# v0_3_1.net
KiCad netlist of a schematic drawn in EAGLE
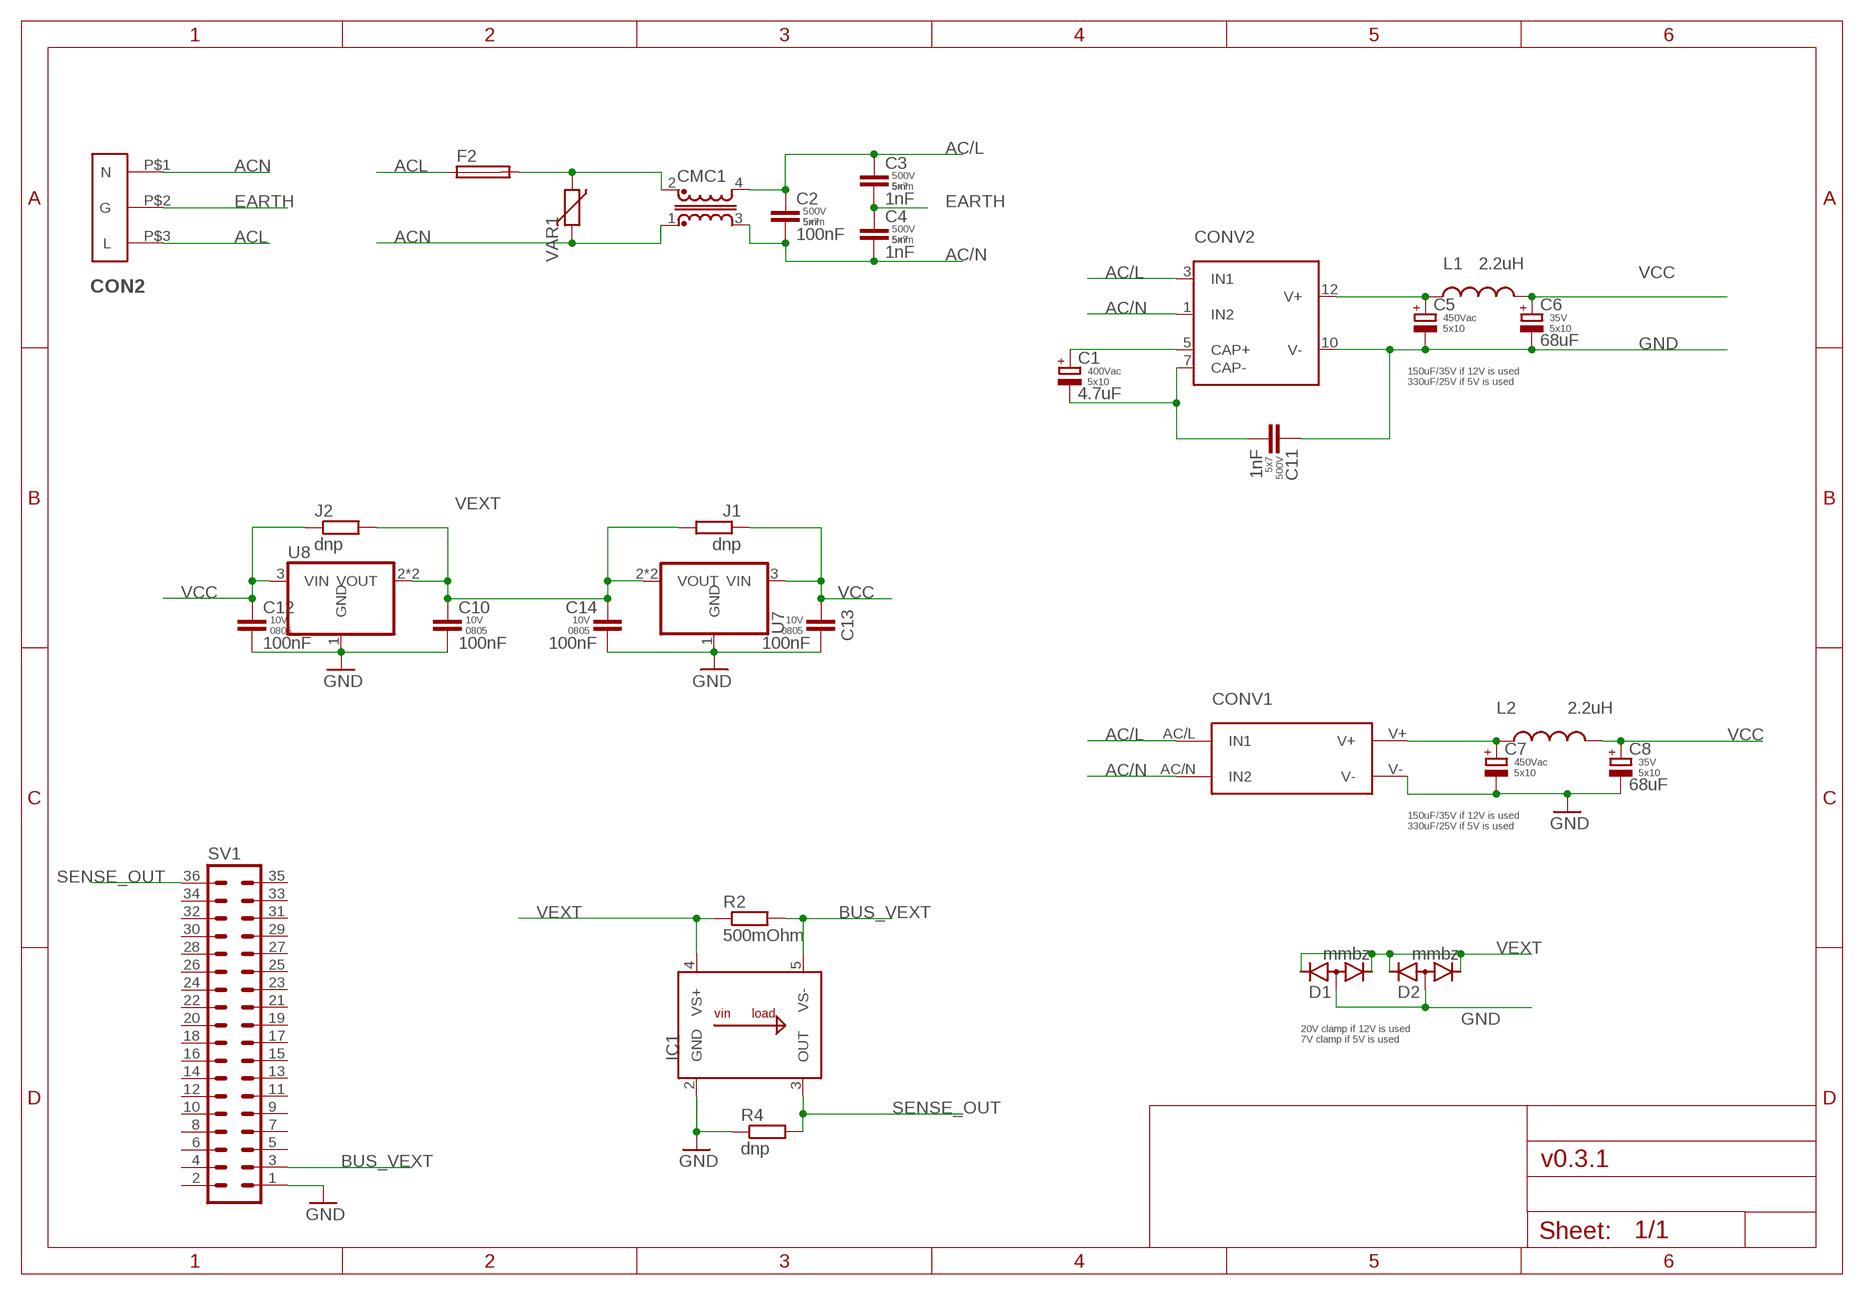
[diagram p0: schematic, sheet 1]

(export (version "E")
  (design (tool "Eeschema 10.0.6"))
  (components
    (comp (ref "C1")
      (value "4.7uF")
      (footprint "eagle-import:CAPPRD508W65D1000H1600B")
      (fields
        (field (name "PACKAGE") "5x10")
        (field (name "RATING") "450Vac")
        (field (name "RATING_1") "400Vac")
      )
      (libsource (lib "eagle-import") (part "CAP-POL-5PX10WX16H"))
    )
    (comp (ref "C2")
      (value "100nF")
      (footprint "eagle-import:C050-025X075")
      (fields
        (field (name "RATING") "500V")
        (field (name "DIMENSIONS") "5mm")
        (field (name "RATING_1") "500V")
      )
      (libsource (lib "eagle-import") (part "CAP-P5W6H8T2.5"))
    )
    (comp (ref "C3")
      (value "1nF")
      (footprint "eagle-import:C050-025X075")
      (fields
        (field (name "RATING") "500V")
        (field (name "DIMENSIONS") "5mm")
        (field (name "RATING_1") "500V")
      )
      (libsource (lib "eagle-import") (part "CAP-P5W6H8T2.5"))
    )
    (comp (ref "C4")
      (value "1nF")
      (footprint "eagle-import:C050-025X075")
      (fields
        (field (name "RATING") "500V")
        (field (name "DIMENSIONS") "5mm")
        (field (name "RATING_1") "500V")
      )
      (libsource (lib "eagle-import") (part "CAP-P5W6H8T2.5"))
    )
    (comp (ref "C5")
      (value "CAP-POL-5PX10WX16H")
      (footprint "eagle-import:CAPPRD508W65D1000H1600B")
      (libsource (lib "eagle-import") (part "CAP-POL-5PX10WX16H"))
    )
    (comp (ref "C6")
      (value "68uF")
      (footprint "eagle-import:CAPPRD508W65D1000H1600B")
      (fields
        (field (name "PACKAGE") "5x10")
        (field (name "RATING") "450Vac")
        (field (name "RATING_1") "35V")
      )
      (libsource (lib "eagle-import") (part "CAP-POL-5PX10WX16H"))
    )
    (comp (ref "C7")
      (value "CAP-POL-5PX10WX16H")
      (footprint "eagle-import:CAPPRD508W65D1000H1600B")
      (libsource (lib "eagle-import") (part "CAP-POL-5PX10WX16H"))
    )
    (comp (ref "C8")
      (value "68uF")
      (footprint "eagle-import:CAPPRD508W65D1000H1600B")
      (fields
        (field (name "PACKAGE") "5x10")
        (field (name "RATING") "450Vac")
        (field (name "RATING_1") "35V")
      )
      (libsource (lib "eagle-import") (part "CAP-POL-5PX10WX16H"))
    )
    (comp (ref "C10")
      (value "100nF")
      (footprint "eagle-import:C0805")
      (fields (field (name "RATING") "10V") (field (name "PACKAGE") "0805"))
      (libsource (lib "eagle-import") (part "CAP-0805"))
    )
    (comp (ref "C11")
      (value "1nF")
      (footprint "eagle-import:C050-025X075")
      (fields (field (name "RATING") "500V") (field (name "PACKAGE") "5x7"))
      (libsource (lib "eagle-import") (part "CAP-P5W6H8T2.5"))
    )
    (comp (ref "C12")
      (value "100nF")
      (footprint "eagle-import:C0805")
      (libsource (lib "eagle-import") (part "CAP-0805"))
    )
    (comp (ref "C13")
      (value "100nF")
      (footprint "eagle-import:C0805")
      (libsource (lib "eagle-import") (part "CAP-0805"))
    )
    (comp (ref "C14")
      (value "100nF")
      (footprint "eagle-import:C0805")
      (fields (field (name "RATING") "10V") (field (name "PACKAGE") "0805"))
      (libsource (lib "eagle-import") (part "CAP-0805"))
    )
    (comp (ref "CMC1")
      (value "DLD-302U-1A")
      (footprint "eagle-import:DLD")
      (libsource (lib "eagle-import") (part "DLD-302U-1A"))
    )
    (comp (ref "CON2")
      (value "4300.0101")
      (footprint "eagle-import:IEC-C6")
      (libsource (lib "eagle-import") (part "4300.0101"))
    )
    (comp (ref "CONV1")
      (value "IRM-03-12V")
      (footprint "eagle-import:IRM-03")
      (libsource (lib "eagle-import") (part "IRM-03-12V"))
    )
    (comp (ref "CONV2")
      (value "AMEOF312SJZ")
      (footprint "eagle-import:AMEOF3-JZ")
      (libsource (lib "eagle-import") (part "AMEOF312SJZ"))
    )
    (comp (ref "D1")
      (value "mmbz")
      (footprint "eagle-import:SOT23")
      (libsource (lib "eagle-import") (part "DIODE-2CA|ACSOT23"))
    )
    (comp (ref "D2")
      (value "mmbz")
      (footprint "eagle-import:SOT23")
      (libsource (lib "eagle-import") (part "DIODE-2CA|ACSOT23"))
    )
    (comp (ref "F2")
      (value "ZH8")
      (footprint "eagle-import:ZH8X2")
      (libsource (lib "eagle-import") (part "ZH8"))
    )
    (comp (ref "IC1")
      (value "ZXCT1021")
      (footprint "eagle-import:SOT95P240X110-5")
      (libsource (lib "eagle-import") (part "ZXCT1021"))
    )
    (comp (ref "J1")
      (value "dnp")
      (footprint "eagle-import:R0805")
      (libsource (lib "eagle-import") (part "R-EU_R0805"))
    )
    (comp (ref "J2")
      (value "dnp")
      (footprint "eagle-import:R0805")
      (libsource (lib "eagle-import") (part "R-EU_R0805"))
    )
    (comp (ref "L1")
      (value "2.2uH")
      (footprint "eagle-import:COIL0608")
      (libsource (lib "eagle-import") (part "COIL0608-0.022"))
    )
    (comp (ref "L2")
      (value "2.2uH")
      (footprint "eagle-import:COIL0608")
      (libsource (lib "eagle-import") (part "COIL0608-0.022"))
    )
    (comp (ref "R2")
      (value "500mOhm")
      (footprint "eagle-import:R0805")
      (libsource (lib "eagle-import") (part "R-EU_R0805"))
    )
    (comp (ref "R4")
      (value "dnp")
      (footprint "eagle-import:R0603")
      (libsource (lib "eagle-import") (part "R-EU_R0603"))
    )
    (comp (ref "SV1")
      (value "MA18-2")
      (footprint "eagle-import:MA18-2")
      (libsource (lib "eagle-import") (part "MA18-2"))
    )
    (comp (ref "U7")
      (value "LD1117S50")
      (footprint "eagle-import:SOT230P700X180-4")
      (libsource (lib "eagle-import") (part "LD1117S50"))
    )
    (comp (ref "U8")
      (value "LD1117S50")
      (footprint "eagle-import:SOT230P700X180-4")
      (libsource (lib "eagle-import") (part "LD1117S50"))
    )
    (comp (ref "VAR1")
      (value "S14K250")
      (footprint "eagle-import:C7.5B4")
      (libsource (lib "eagle-import") (part "S14K250"))
    )
  )
  (nets
    (net (code "1") (name "/ACL") (class "Default")
      (node (ref "CON2") (pin "P$3") (pinfunction "L_P$3") (pintype "bidirectional"))
      (node (ref "F2") (pin "1") (pinfunction "1_1") (pintype "passive"))
      (node (ref "F2") (pin "1A") (pinfunction "1_1A") (pintype "passive"))
    )
    (net (code "2") (name "/ACN") (class "Default")
      (node (ref "CMC1") (pin "1") (pinfunction "1_1") (pintype "passive"))
      (node (ref "CON2") (pin "P$1") (pinfunction "N_P$1") (pintype "bidirectional"))
      (node (ref "VAR1") (pin "1") (pinfunction "1_1") (pintype "passive"))
    )
    (net (code "3") (name "/AC{slash}L") (class "Default")
      (node (ref "C2") (pin "1") (pinfunction "1_1") (pintype "passive"))
      (node (ref "C3") (pin "1") (pinfunction "1_1") (pintype "passive"))
      (node (ref "CMC1") (pin "4") (pinfunction "4_4") (pintype "passive"))
      (node (ref "CONV1") (pin "AC/L") (pinfunction "IN1_AC/L") (pintype "bidirectional"))
      (node (ref "CONV2") (pin "3") (pinfunction "IN1_3") (pintype "bidirectional"))
    )
    (net (code "4") (name "/AC{slash}N") (class "Default")
      (node (ref "C2") (pin "2") (pinfunction "2_2") (pintype "passive"))
      (node (ref "C4") (pin "2") (pinfunction "2_2") (pintype "passive"))
      (node (ref "CMC1") (pin "3") (pinfunction "3_3") (pintype "passive"))
      (node (ref "CONV1") (pin "AC/N") (pinfunction "IN2_AC/N") (pintype "bidirectional"))
      (node (ref "CONV2") (pin "1") (pinfunction "IN2_1") (pintype "bidirectional"))
    )
    (net (code "5") (name "/BUS_VEXT") (class "Default")
      (node (ref "IC1") (pin "5") (pinfunction "VS-_5") (pintype "bidirectional"))
      (node (ref "R2") (pin "2") (pinfunction "2_2") (pintype "passive"))
      (node (ref "SV1") (pin "3") (pinfunction "3_3") (pintype "passive"))
    )
    (net (code "6") (name "/EARTH") (class "Default")
      (node (ref "C3") (pin "2") (pinfunction "2_2") (pintype "passive"))
      (node (ref "C4") (pin "1") (pinfunction "1_1") (pintype "passive"))
      (node (ref "CON2") (pin "P$2") (pinfunction "G_P$2") (pintype "bidirectional"))
    )
    (net (code "7") (name "/SENSE_OUT") (class "Default")
      (node (ref "IC1") (pin "3") (pinfunction "OUT_3") (pintype "bidirectional"))
      (node (ref "R4") (pin "2") (pinfunction "2_2") (pintype "passive"))
      (node (ref "SV1") (pin "36") (pinfunction "36_36") (pintype "passive"))
    )
    (net (code "8") (name "/VCC") (class "Default")
      (node (ref "C12") (pin "1") (pinfunction "1_1") (pintype "passive"))
      (node (ref "C13") (pin "1") (pinfunction "1_1") (pintype "passive"))
      (node (ref "C6") (pin "1") (pinfunction "+_1") (pintype "passive"))
      (node (ref "C8") (pin "1") (pinfunction "+_1") (pintype "passive"))
      (node (ref "J1") (pin "1") (pinfunction "1_1") (pintype "passive"))
      (node (ref "J2") (pin "1") (pinfunction "1_1") (pintype "passive"))
      (node (ref "L1") (pin "P$2") (pinfunction "2_P$2") (pintype "passive"))
      (node (ref "L2") (pin "P$2") (pinfunction "2_P$2") (pintype "passive"))
      (node (ref "U7") (pin "3") (pinfunction "VIN_3") (pintype "input"))
      (node (ref "U8") (pin "3") (pinfunction "VIN_3") (pintype "input"))
    )
    (net (code "9") (name "/VEXT") (class "Default")
      (node (ref "C10") (pin "1") (pinfunction "1_1") (pintype "passive"))
      (node (ref "C14") (pin "1") (pinfunction "1_1") (pintype "passive"))
      (node (ref "D1") (pin "1") (pinfunction "K1_1") (pintype "passive"))
      (node (ref "D1") (pin "2") (pinfunction "K2_2") (pintype "passive"))
      (node (ref "D2") (pin "1") (pinfunction "K1_1") (pintype "passive"))
      (node (ref "D2") (pin "2") (pinfunction "K2_2") (pintype "passive"))
      (node (ref "IC1") (pin "4") (pinfunction "VS+_4") (pintype "bidirectional"))
      (node (ref "J1") (pin "2") (pinfunction "2_2") (pintype "passive"))
      (node (ref "J2") (pin "2") (pinfunction "2_2") (pintype "passive"))
      (node (ref "R2") (pin "1") (pinfunction "1_1") (pintype "passive"))
      (node (ref "U7") (pin "2") (pinfunction "VOUT_2") (pintype "output"))
      (node (ref "U7") (pin "4") (pinfunction "VOUT_4") (pintype "output"))
      (node (ref "U8") (pin "2") (pinfunction "VOUT_2") (pintype "output"))
      (node (ref "U8") (pin "4") (pinfunction "VOUT_4") (pintype "output"))
    )
    (net (code "10") (name "GND") (class "Default")
      (node (ref "C10") (pin "2") (pinfunction "2_2") (pintype "passive"))
      (node (ref "C11") (pin "1") (pinfunction "1_1") (pintype "passive"))
      (node (ref "C12") (pin "2") (pinfunction "2_2") (pintype "passive"))
      (node (ref "C13") (pin "2") (pinfunction "2_2") (pintype "passive"))
      (node (ref "C14") (pin "2") (pinfunction "2_2") (pintype "passive"))
      (node (ref "C5") (pin "2") (pinfunction "-_2") (pintype "passive"))
      (node (ref "C6") (pin "2") (pinfunction "-_2") (pintype "passive"))
      (node (ref "C7") (pin "2") (pinfunction "-_2") (pintype "passive"))
      (node (ref "C8") (pin "2") (pinfunction "-_2") (pintype "passive"))
      (node (ref "CONV1") (pin "V-") (pinfunction "V-_V-") (pintype "bidirectional"))
      (node (ref "CONV2") (pin "10") (pinfunction "V-_10") (pintype "bidirectional"))
      (node (ref "D1") (pin "3") (pinfunction "A_3") (pintype "passive"))
      (node (ref "D2") (pin "3") (pinfunction "A_3") (pintype "passive"))
      (node (ref "IC1") (pin "2") (pinfunction "GND_2") (pintype "bidirectional"))
      (node (ref "R4") (pin "1") (pinfunction "1_1") (pintype "passive"))
      (node (ref "SV1") (pin "1") (pinfunction "1_1") (pintype "passive"))
      (node (ref "U7") (pin "1") (pinfunction "GND_1") (pintype "power_in"))
      (node (ref "U8") (pin "1") (pinfunction "GND_1") (pintype "power_in"))
    )
    (net (code "11") (name "Net-(C1-+)") (class "Default")
      (node (ref "C1") (pin "1") (pinfunction "+_1") (pintype "passive"))
      (node (ref "CONV2") (pin "5") (pinfunction "CAP+_5") (pintype "bidirectional"))
    )
    (net (code "12") (name "Net-(C1--)") (class "Default")
      (node (ref "C1") (pin "2") (pinfunction "-_2") (pintype "passive"))
      (node (ref "C11") (pin "2") (pinfunction "2_2") (pintype "passive"))
      (node (ref "CONV2") (pin "7") (pinfunction "CAP-_7") (pintype "bidirectional"))
    )
    (net (code "13") (name "Net-(C5-+)") (class "Default")
      (node (ref "C5") (pin "1") (pinfunction "+_1") (pintype "passive"))
      (node (ref "CONV2") (pin "12") (pinfunction "V+_12") (pintype "bidirectional"))
      (node (ref "L1") (pin "P$1") (pinfunction "1_P$1") (pintype "passive"))
    )
    (net (code "14") (name "Net-(C7-+)") (class "Default")
      (node (ref "C7") (pin "1") (pinfunction "+_1") (pintype "passive"))
      (node (ref "CONV1") (pin "V+") (pinfunction "V+_V+") (pintype "bidirectional"))
      (node (ref "L2") (pin "P$1") (pinfunction "1_P$1") (pintype "passive"))
    )
    (net (code "15") (name "Net-(CMC1-Pad2)") (class "Default")
      (node (ref "CMC1") (pin "2") (pinfunction "2_2") (pintype "passive"))
      (node (ref "F2") (pin "2") (pinfunction "2_2") (pintype "passive"))
      (node (ref "F2") (pin "2A") (pinfunction "2_2A") (pintype "passive"))
      (node (ref "VAR1") (pin "2") (pinfunction "2_2") (pintype "passive"))
    )
    (net (code "16") (name "unconnected-(SV1-Pad2)") (class "Default")
      (node (ref "SV1") (pin "2") (pinfunction "2_2") (pintype "passive"))
    )
    (net (code "17") (name "unconnected-(SV1-Pad4)") (class "Default")
      (node (ref "SV1") (pin "4") (pinfunction "4_4") (pintype "passive"))
    )
    (net (code "18") (name "unconnected-(SV1-Pad5)") (class "Default")
      (node (ref "SV1") (pin "5") (pinfunction "5_5") (pintype "passive"))
    )
    (net (code "19") (name "unconnected-(SV1-Pad6)") (class "Default")
      (node (ref "SV1") (pin "6") (pinfunction "6_6") (pintype "passive"))
    )
    (net (code "20") (name "unconnected-(SV1-Pad7)") (class "Default")
      (node (ref "SV1") (pin "7") (pinfunction "7_7") (pintype "passive"))
    )
    (net (code "21") (name "unconnected-(SV1-Pad8)") (class "Default")
      (node (ref "SV1") (pin "8") (pinfunction "8_8") (pintype "passive"))
    )
    (net (code "22") (name "unconnected-(SV1-Pad9)") (class "Default")
      (node (ref "SV1") (pin "9") (pinfunction "9_9") (pintype "passive"))
    )
    (net (code "23") (name "unconnected-(SV1-Pad10)") (class "Default")
      (node (ref "SV1") (pin "10") (pinfunction "10_10") (pintype "passive"))
    )
    (net (code "24") (name "unconnected-(SV1-Pad11)") (class "Default")
      (node (ref "SV1") (pin "11") (pinfunction "11_11") (pintype "passive"))
    )
    (net (code "25") (name "unconnected-(SV1-Pad12)") (class "Default")
      (node (ref "SV1") (pin "12") (pinfunction "12_12") (pintype "passive"))
    )
    (net (code "26") (name "unconnected-(SV1-Pad13)") (class "Default")
      (node (ref "SV1") (pin "13") (pinfunction "13_13") (pintype "passive"))
    )
    (net (code "27") (name "unconnected-(SV1-Pad14)") (class "Default")
      (node (ref "SV1") (pin "14") (pinfunction "14_14") (pintype "passive"))
    )
    (net (code "28") (name "unconnected-(SV1-Pad15)") (class "Default")
      (node (ref "SV1") (pin "15") (pinfunction "15_15") (pintype "passive"))
    )
    (net (code "29") (name "unconnected-(SV1-Pad16)") (class "Default")
      (node (ref "SV1") (pin "16") (pinfunction "16_16") (pintype "passive"))
    )
    (net (code "30") (name "unconnected-(SV1-Pad17)") (class "Default")
      (node (ref "SV1") (pin "17") (pinfunction "17_17") (pintype "passive"))
    )
    (net (code "31") (name "unconnected-(SV1-Pad18)") (class "Default")
      (node (ref "SV1") (pin "18") (pinfunction "18_18") (pintype "passive"))
    )
    (net (code "32") (name "unconnected-(SV1-Pad19)") (class "Default")
      (node (ref "SV1") (pin "19") (pinfunction "19_19") (pintype "passive"))
    )
    (net (code "33") (name "unconnected-(SV1-Pad20)") (class "Default")
      (node (ref "SV1") (pin "20") (pinfunction "20_20") (pintype "passive"))
    )
    (net (code "34") (name "unconnected-(SV1-Pad21)") (class "Default")
      (node (ref "SV1") (pin "21") (pinfunction "21_21") (pintype "passive"))
    )
    (net (code "35") (name "unconnected-(SV1-Pad22)") (class "Default")
      (node (ref "SV1") (pin "22") (pinfunction "22_22") (pintype "passive"))
    )
    (net (code "36") (name "unconnected-(SV1-Pad23)") (class "Default")
      (node (ref "SV1") (pin "23") (pinfunction "23_23") (pintype "passive"))
    )
    (net (code "37") (name "unconnected-(SV1-Pad24)") (class "Default")
      (node (ref "SV1") (pin "24") (pinfunction "24_24") (pintype "passive"))
    )
    (net (code "38") (name "unconnected-(SV1-Pad25)") (class "Default")
      (node (ref "SV1") (pin "25") (pinfunction "25_25") (pintype "passive"))
    )
    (net (code "39") (name "unconnected-(SV1-Pad26)") (class "Default")
      (node (ref "SV1") (pin "26") (pinfunction "26_26") (pintype "passive"))
    )
    (net (code "40") (name "unconnected-(SV1-Pad27)") (class "Default")
      (node (ref "SV1") (pin "27") (pinfunction "27_27") (pintype "passive"))
    )
    (net (code "41") (name "unconnected-(SV1-Pad28)") (class "Default")
      (node (ref "SV1") (pin "28") (pinfunction "28_28") (pintype "passive"))
    )
    (net (code "42") (name "unconnected-(SV1-Pad29)") (class "Default")
      (node (ref "SV1") (pin "29") (pinfunction "29_29") (pintype "passive"))
    )
    (net (code "43") (name "unconnected-(SV1-Pad30)") (class "Default")
      (node (ref "SV1") (pin "30") (pinfunction "30_30") (pintype "passive"))
    )
    (net (code "44") (name "unconnected-(SV1-Pad31)") (class "Default")
      (node (ref "SV1") (pin "31") (pinfunction "31_31") (pintype "passive"))
    )
    (net (code "45") (name "unconnected-(SV1-Pad32)") (class "Default")
      (node (ref "SV1") (pin "32") (pinfunction "32_32") (pintype "passive"))
    )
    (net (code "46") (name "unconnected-(SV1-Pad33)") (class "Default")
      (node (ref "SV1") (pin "33") (pinfunction "33_33") (pintype "passive"))
    )
    (net (code "47") (name "unconnected-(SV1-Pad34)") (class "Default")
      (node (ref "SV1") (pin "34") (pinfunction "34_34") (pintype "passive"))
    )
    (net (code "48") (name "unconnected-(SV1-Pad35)") (class "Default")
      (node (ref "SV1") (pin "35") (pinfunction "35_35") (pintype "passive"))
    )
  )
)
